# S7CAS-PLEIADES-CARTE-MERE_Pxx_FLASH_PHY_.net
KiCad netlist of a schematic drawn in Altium Designer
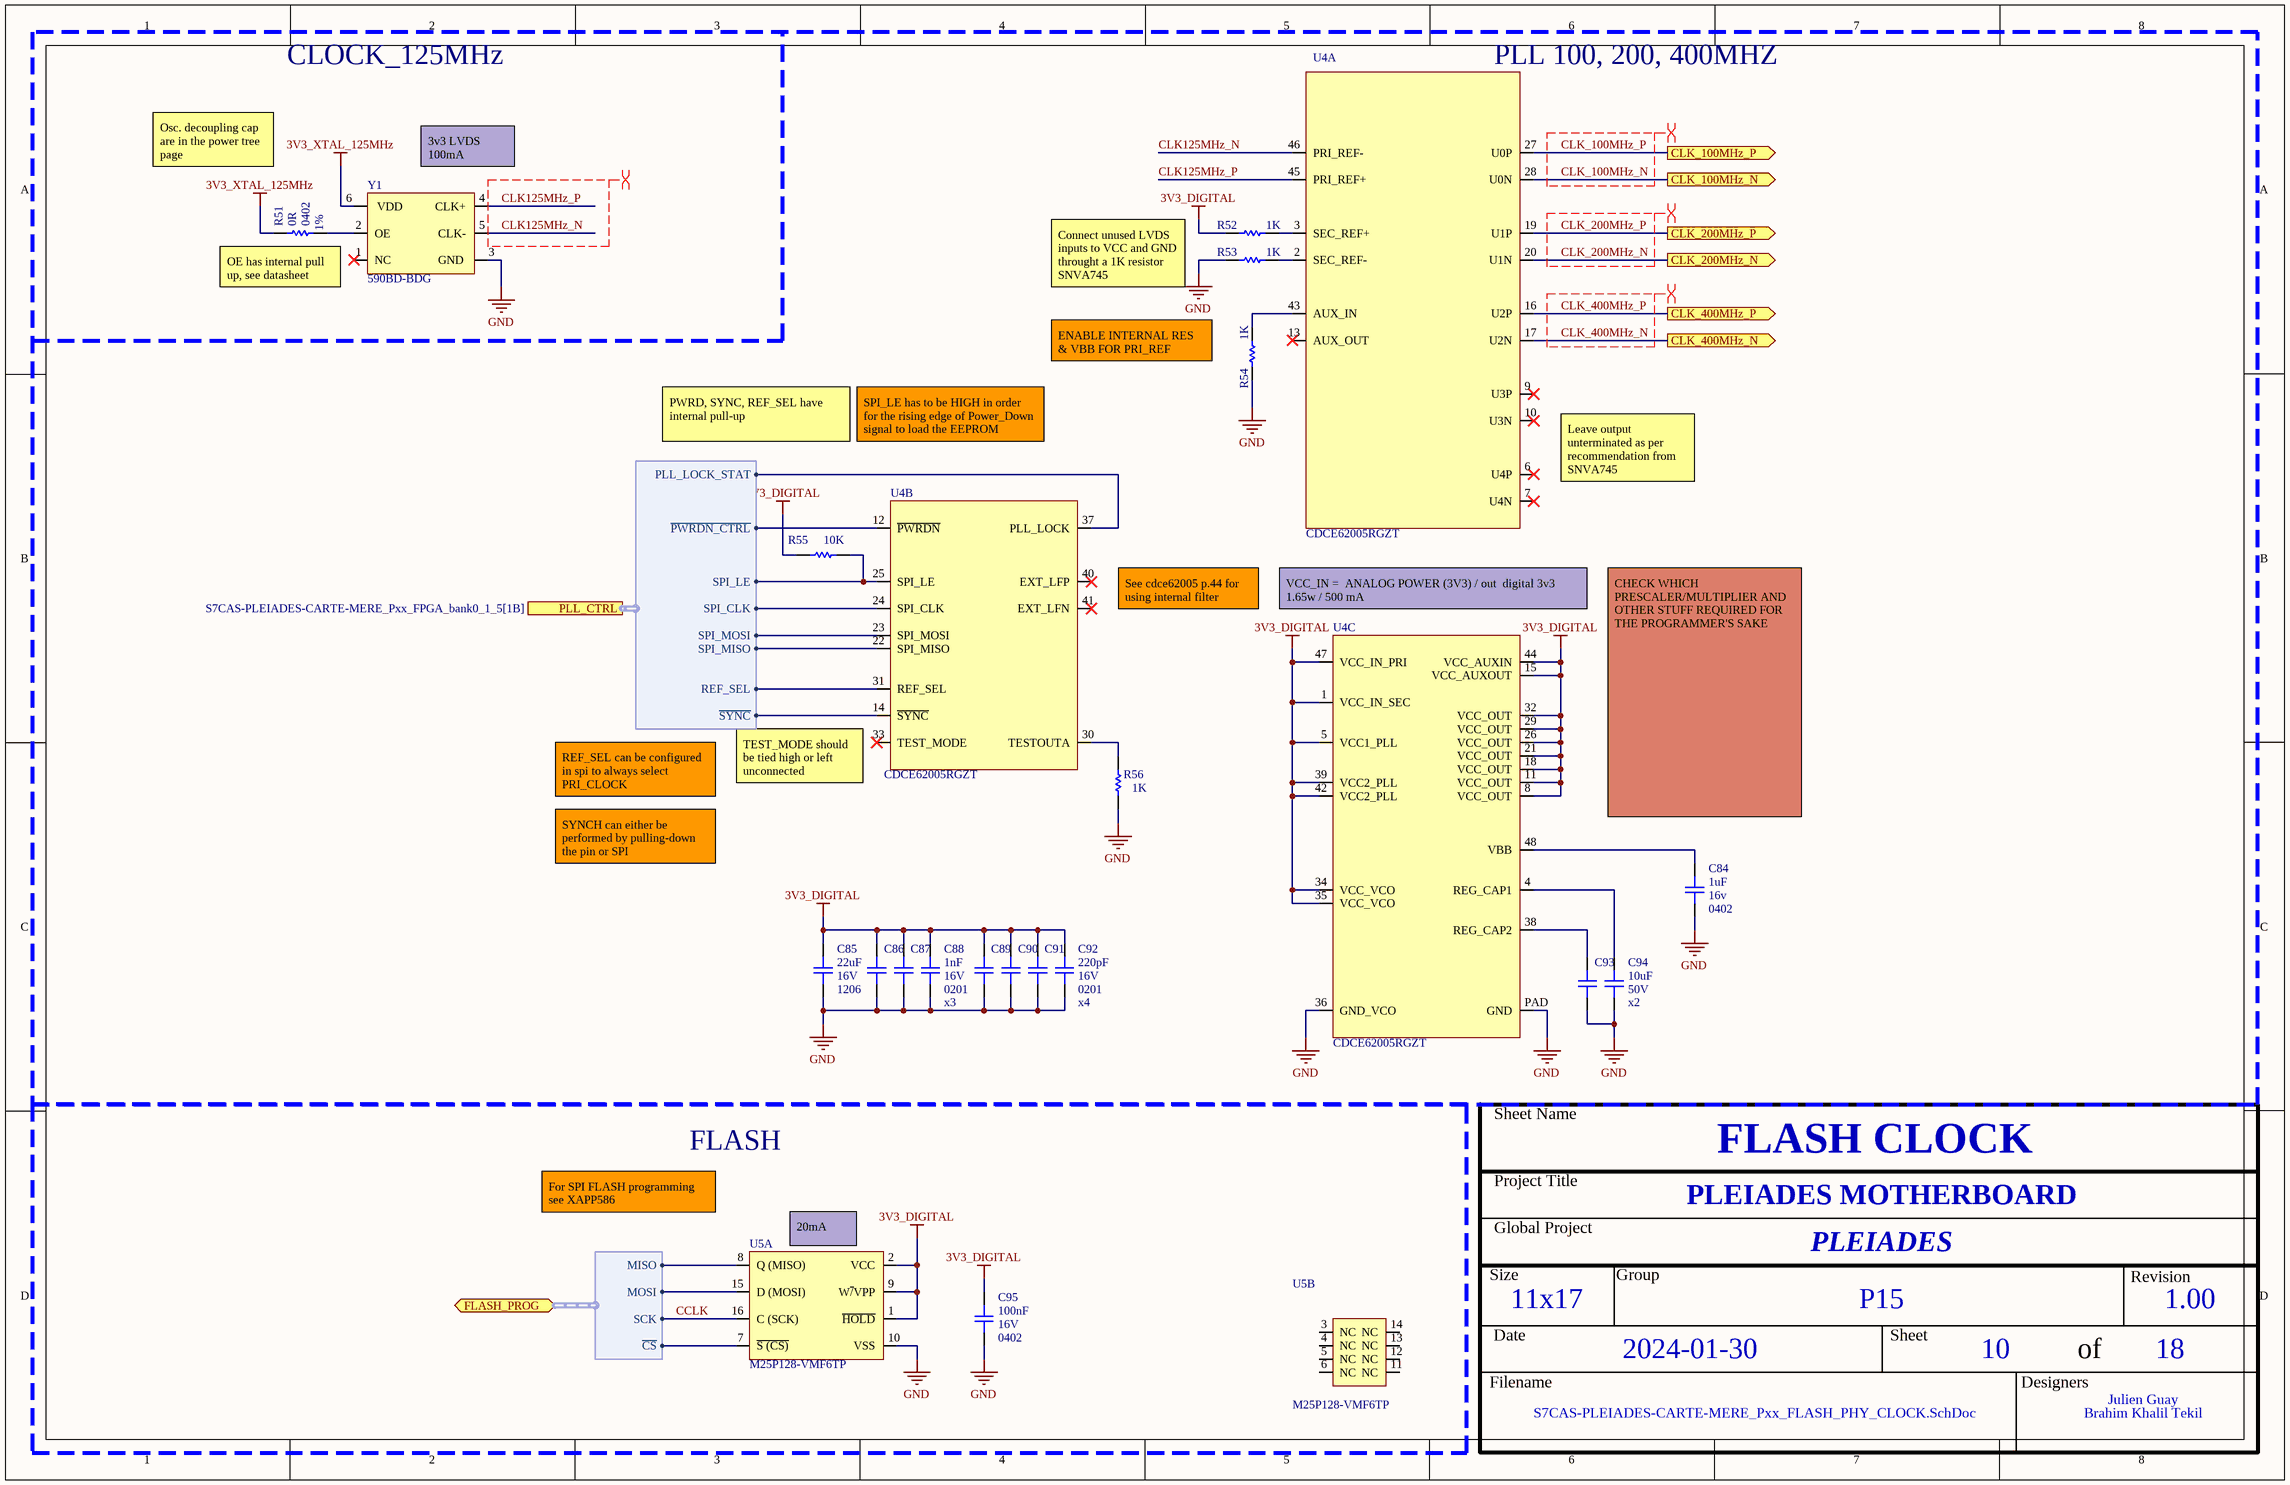
[diagram p0: S7CAS-PLEIADES-CARTE-MERE_Pxx_FLASH_PHY_CLOCK.SchDoc]

(export (version "E")
  (design (tool "Eeschema 10.0.6"))
  (components
    (comp (ref "C84")
      (value "1uF")
      (footprint "S7CAS_LIB2023:CAP_0402")
      (description "CAP - 0402")
      (fields
        (field (name "VOLTAGE") "16v")
        (field (name "PACKAGE") "0402")
        (field (name "Comment") "0402")
        (field (name "CREATEDBY") "Jonathan Bouchard")
      )
      (libsource (lib "S7CAS_LIB2023") (part "CAP - 0603"))
    )
    (comp (ref "C85")
      (value "22uF")
      (footprint "S7CAS_LIB2023:CAP_1206")
      (description "CAP - 1206")
      (fields
        (field (name "VOLTAGE") "16V")
        (field (name "PACKAGE") "1206")
        (field (name "CREATEDBY") "Jonathan Bouchard")
      )
      (libsource (lib "S7CAS_LIB2023") (part "CAP - 1206"))
    )
    (comp (ref "C86")
      (value "CAP - 0201")
      (footprint "CAP_0201")
      (fields (field (name "VOLTAGE") "16V") (field (name "CREATEDBY") "Jonathan Bouchard"))
      (libsource (lib "S7CAS_LIB2023") (part "CAP - 0201"))
    )
    (comp (ref "C87")
      (value "CAP - 0201")
      (footprint "CAP_0201")
      (fields (field (name "VOLTAGE") "16V") (field (name "CREATEDBY") "Jonathan Bouchard"))
      (libsource (lib "S7CAS_LIB2023") (part "CAP - 0201"))
    )
    (comp (ref "C88")
      (value "1nF")
      (footprint "CAP_0201")
      (description "CAP - 0201")
      (fields
        (field (name "VOLTAGE") "16V")
        (field (name "PACKAGE") "0201")
        (field (name "CREATEDBY") "Jonathan Bouchard")
      )
      (libsource (lib "S7CAS_LIB2023") (part "CAP - 0201"))
    )
    (comp (ref "C89")
      (value "CAP - 0201")
      (footprint "CAP_0201")
      (fields (field (name "VOLTAGE") "16V") (field (name "CREATEDBY") "Jonathan Bouchard"))
      (libsource (lib "S7CAS_LIB2023") (part "CAP - 0201"))
    )
    (comp (ref "C90")
      (value "CAP - 0201")
      (footprint "CAP_0201")
      (fields (field (name "VOLTAGE") "16V") (field (name "CREATEDBY") "Jonathan Bouchard"))
      (libsource (lib "S7CAS_LIB2023") (part "CAP - 0201"))
    )
    (comp (ref "C91")
      (value "CAP - 0201")
      (footprint "CAP_0201")
      (fields (field (name "VOLTAGE") "16V") (field (name "CREATEDBY") "Jonathan Bouchard"))
      (libsource (lib "S7CAS_LIB2023") (part "CAP - 0201"))
    )
    (comp (ref "C92")
      (value "220pF")
      (footprint "CAP_0201")
      (description "CAP - 0201")
      (fields
        (field (name "VOLTAGE") "16V")
        (field (name "PACKAGE") "0201")
        (field (name "CREATEDBY") "Jonathan Bouchard")
      )
      (libsource (lib "S7CAS_LIB2023") (part "CAP - 0201"))
    )
    (comp (ref "C93")
      (value "CAP - 1206")
      (footprint "S7CAS_LIB2023:CAP_1206")
      (fields (field (name "VOLTAGE") "50V") (field (name "CREATEDBY") "Jonathan Bouchard"))
      (libsource (lib "S7CAS_LIB2023") (part "CAP - 1206"))
    )
    (comp (ref "C94")
      (value "10uF")
      (footprint "S7CAS_LIB2023:CAP_1206")
      (description "CAP - 1206")
      (fields (field (name "VOLTAGE") "50V") (field (name "CREATEDBY") "Jonathan Bouchard"))
      (libsource (lib "S7CAS_LIB2023") (part "CAP - 1206"))
    )
    (comp (ref "C95")
      (value "100nF")
      (footprint "S7CAS_LIB2023:CAP_0402")
      (description "CAP - 0402")
      (fields
        (field (name "VOLTAGE") "16V")
        (field (name "PACKAGE") "0402")
        (field (name "Comment") "0402")
        (field (name "CREATEDBY") "Jonathan Bouchard")
      )
      (libsource (lib "S7CAS_LIB2023") (part "CAP - 0603"))
    )
    (comp (ref "R51")
      (value "0R")
      (footprint "S7CAS_LIB2023:RES_0402")
      (description "RES - 0402")
      (fields
        (field (name "PACKAGE") "0402")
        (field (name "PRECISION") "1%")
        (field (name "Comment") "RES - 0603")
        (field (name "CREATEDBY") "Jonathan Bouchard")
      )
      (libsource (lib "S7CAS_LIB2023") (part "RES - 0603"))
    )
    (comp (ref "R52")
      (value "1K")
      (footprint "S7CAS_LIB2023:RES_0402")
      (description "RES - 0402")
      (fields (field (name "Comment") "RES - 0603") (field (name "CREATEDBY") "Jonathan Bouchard"))
      (libsource (lib "S7CAS_LIB2023") (part "RES - 0603"))
    )
    (comp (ref "R53")
      (value "1K")
      (footprint "S7CAS_LIB2023:RES_0402")
      (description "RES - 0402")
      (fields (field (name "Comment") "RES - 0603") (field (name "CREATEDBY") "Jonathan Bouchard"))
      (libsource (lib "S7CAS_LIB2023") (part "RES - 0603"))
    )
    (comp (ref "R54")
      (value "1K")
      (footprint "S7CAS_LIB2023:RES_0402")
      (description "RES - 0402")
      (fields (field (name "Comment") "RES - 0603") (field (name "CREATEDBY") "Jonathan Bouchard"))
      (libsource (lib "S7CAS_LIB2023") (part "RES - 0603"))
    )
    (comp (ref "R55")
      (value "10K")
      (footprint "S7CAS_LIB2023:RES_0402")
      (description "RES - 0402")
      (fields (field (name "Comment") "RES - 0603") (field (name "CREATEDBY") "Jonathan Bouchard"))
      (libsource (lib "S7CAS_LIB2023") (part "RES - 0603"))
    )
    (comp (ref "R56")
      (value "1K")
      (footprint "S7CAS_LIB2023:RES_0402")
      (description "RES - 0402")
      (fields (field (name "Comment") "RES - 0603") (field (name "CREATEDBY") "Jonathan Bouchard"))
      (libsource (lib "S7CAS_LIB2023") (part "RES - 0603"))
    )
    (comp (ref "U4")
      (value "CDCE62005RGZT")
      (footprint "TIM_CDCE62005RGZT")
      (description "TIM - CLK SYNTH JITTER CLEANER 3:5 - QFN-48")
      (fields
        (field (name "VOLTAGE") "3 V ~ 3.6 V")
        (field (name "MFG") "Texas Instruments")
        (field (name "CREATEDBY") "Jonathan Bouchard")
      )
      (libsource (lib "S7CAS_LIB2023") (part "TIM_CDCE62005RGZT"))
    )
    (comp (ref "U5")
      (value "M25P128-VMF6TP")
      (footprint "FLASH - M25P128-VMF6TP")
      (description "128-Mbit, low-voltage, serial flash memory\r\nwith 54-MHz SPI bus interface")
      (libsource (lib "S7CAS_LIB2023") (part "FLASH  - M25P128-VMF6TP"))
    )
    (comp (ref "Y1")
      (value "590BD-BDG")
      (footprint "OSC_590BD-BDG")
      (description "TIM - OSC PROG 125MHz ~ 214.999MHz LVDS 3.3V 7PPM EN/DS - 6-SMD")
      (fields
        (field (name "CREATEDBY/DATE") "from 590BD-CDG")
        (field (name "VERIFIEDBY") "Caroline Paulin / 3/10/2019")
      )
      (libsource (lib "S7CAS_LIB2023") (part "OSC_590BD-BDG"))
    )
  )
  (nets
    (net (code "3") (name "/CCLK") (class "Default")
      (node (ref "U5") (pin "16") (pinfunction "C_(SCK)_16") (pintype "passive"))
    )
    (net (code "4") (name "/CLK125MHz_N") (class "Default")
      (node (ref "U4") (pin "46") (pinfunction "PRI_REF-_46") (pintype "passive"))
      (node (ref "Y1") (pin "5") (pinfunction "CLK-_5") (pintype "passive"))
    )
    (net (code "5") (name "/CLK125MHz_P") (class "Default")
      (node (ref "U4") (pin "45") (pinfunction "PRI_REF+_45") (pintype "passive"))
      (node (ref "Y1") (pin "4") (pinfunction "CLK+_4") (pintype "passive"))
    )
    (net (code "6") (name "/CLK_100MHz_N") (class "Default")
      (node (ref "U4") (pin "28") (pinfunction "U0N_28") (pintype "passive"))
    )
    (net (code "7") (name "/CLK_100MHz_P") (class "Default")
      (node (ref "U4") (pin "27") (pinfunction "U0P_27") (pintype "passive"))
    )
    (net (code "8") (name "/CLK_200MHz_N") (class "Default")
      (node (ref "U4") (pin "20") (pinfunction "U1N_20") (pintype "passive"))
    )
    (net (code "9") (name "/CLK_200MHz_P") (class "Default")
      (node (ref "U4") (pin "19") (pinfunction "U1P_19") (pintype "passive"))
    )
    (net (code "10") (name "/CLK_400MHz_N") (class "Default")
      (node (ref "U4") (pin "17") (pinfunction "U2N_17") (pintype "passive"))
    )
    (net (code "11") (name "/CLK_400MHz_P") (class "Default")
      (node (ref "U4") (pin "16") (pinfunction "U2P_16") (pintype "passive"))
    )
    (net (code "12") (name "/MISO") (class "Default")
      (node (ref "U5") (pin "8") (pinfunction "Q_(MISO)_8") (pintype "passive"))
    )
    (net (code "13") (name "/MOSI") (class "Default")
      (node (ref "U5") (pin "15") (pinfunction "D_(MOSI)_15") (pintype "passive"))
    )
    (net (code "14") (name "/PLL_LOCK_STAT") (class "Default")
      (node (ref "U4") (pin "37") (pinfunction "PLL_LOCK_37") (pintype "passive"))
    )
    (net (code "15") (name "/REF_SEL") (class "Default")
      (node (ref "U4") (pin "31") (pinfunction "REF_SEL_31") (pintype "passive"))
    )
    (net (code "16") (name "/SPI_CLK") (class "Default")
      (node (ref "U4") (pin "24") (pinfunction "SPI_CLK_24") (pintype "passive"))
    )
    (net (code "17") (name "/SPI_LE") (class "Default")
      (node (ref "R55") (pin "1") (pinfunction "1_1") (pintype "passive"))
      (node (ref "U4") (pin "25") (pinfunction "SPI_LE_25") (pintype "passive"))
    )
    (net (code "18") (name "/SPI_MISO") (class "Default")
      (node (ref "U4") (pin "22") (pinfunction "SPI_MISO_22") (pintype "passive"))
    )
    (net (code "19") (name "/SPI_MOSI") (class "Default")
      (node (ref "U4") (pin "23") (pinfunction "SPI_MOSI_23") (pintype "passive"))
    )
    (net (code "22") (name "/~{CS}") (class "Default")
      (node (ref "U5") (pin "7") (pinfunction "S_(CS)_7") (pintype "passive"))
    )
    (net (code "23") (name "/~{PWRDN_CTRL}") (class "Default")
      (node (ref "U4") (pin "12") (pinfunction "~{PWRDN}_12") (pintype "passive"))
    )
    (net (code "24") (name "/~{SYNC}") (class "Default")
      (node (ref "U4") (pin "14") (pinfunction "~{SYNC}_14") (pintype "passive"))
    )
    (net (code "25") (name "3V3_DIGITAL") (class "Default")
      (node (ref "C85") (pin "2") (pinfunction "2_2") (pintype "passive"))
      (node (ref "C86") (pin "2") (pinfunction "2_2") (pintype "passive"))
      (node (ref "C87") (pin "2") (pinfunction "2_2") (pintype "passive"))
      (node (ref "C88") (pin "2") (pinfunction "2_2") (pintype "passive"))
      (node (ref "C89") (pin "2") (pinfunction "2_2") (pintype "passive"))
      (node (ref "C90") (pin "2") (pinfunction "2_2") (pintype "passive"))
      (node (ref "C91") (pin "2") (pinfunction "2_2") (pintype "passive"))
      (node (ref "C92") (pin "2") (pinfunction "2_2") (pintype "passive"))
      (node (ref "C95") (pin "2") (pinfunction "2_2") (pintype "passive"))
      (node (ref "R52") (pin "2") (pinfunction "2_2") (pintype "passive"))
      (node (ref "R55") (pin "2") (pinfunction "2_2") (pintype "passive"))
      (node (ref "U4") (pin "1") (pinfunction "VCC_IN_SEC_1") (pintype "passive"))
      (node (ref "U4") (pin "11") (pinfunction "VCC_OUT_11") (pintype "passive"))
      (node (ref "U4") (pin "15") (pinfunction "VCC_AUXOUT_15") (pintype "passive"))
      (node (ref "U4") (pin "18") (pinfunction "VCC_OUT_18") (pintype "passive"))
      (node (ref "U4") (pin "21") (pinfunction "VCC_OUT_21") (pintype "passive"))
      (node (ref "U4") (pin "26") (pinfunction "VCC_OUT_26") (pintype "passive"))
      (node (ref "U4") (pin "29") (pinfunction "VCC_OUT_29") (pintype "passive"))
      (node (ref "U4") (pin "32") (pinfunction "VCC_OUT_32") (pintype "passive"))
      (node (ref "U4") (pin "34") (pinfunction "VCC_VCO_34") (pintype "passive"))
      (node (ref "U4") (pin "35") (pinfunction "VCC_VCO_35") (pintype "passive"))
      (node (ref "U4") (pin "39") (pinfunction "VCC2_PLL_39") (pintype "passive"))
      (node (ref "U4") (pin "42") (pinfunction "VCC2_PLL_42") (pintype "passive"))
      (node (ref "U4") (pin "44") (pinfunction "VCC_AUXIN_44") (pintype "passive"))
      (node (ref "U4") (pin "47") (pinfunction "VCC_IN_PRI_47") (pintype "passive"))
      (node (ref "U4") (pin "5") (pinfunction "VCC1_PLL_5") (pintype "passive"))
      (node (ref "U4") (pin "8") (pinfunction "VCC_OUT_8") (pintype "passive"))
      (node (ref "U5") (pin "1") (pinfunction "HOLD_1") (pintype "passive"))
      (node (ref "U5") (pin "2") (pinfunction "VCC_2") (pintype "power_in"))
      (node (ref "U5") (pin "9") (pinfunction "W~{/}VPP_9") (pintype "passive"))
    )
    (net (code "26") (name "3V3_XTAL_125MHz") (class "Default")
      (node (ref "R51") (pin "2") (pinfunction "2_2") (pintype "passive"))
      (node (ref "Y1") (pin "6") (pinfunction "VDD_6") (pintype "passive"))
    )
    (net (code "27") (name "GND") (class "Default")
      (node (ref "C84") (pin "1") (pinfunction "1_1") (pintype "passive"))
      (node (ref "C85") (pin "1") (pinfunction "1_1") (pintype "passive"))
      (node (ref "C86") (pin "1") (pinfunction "1_1") (pintype "passive"))
      (node (ref "C87") (pin "1") (pinfunction "1_1") (pintype "passive"))
      (node (ref "C88") (pin "1") (pinfunction "1_1") (pintype "passive"))
      (node (ref "C89") (pin "1") (pinfunction "1_1") (pintype "passive"))
      (node (ref "C90") (pin "1") (pinfunction "1_1") (pintype "passive"))
      (node (ref "C91") (pin "1") (pinfunction "1_1") (pintype "passive"))
      (node (ref "C92") (pin "1") (pinfunction "1_1") (pintype "passive"))
      (node (ref "C93") (pin "1") (pinfunction "1_1") (pintype "passive"))
      (node (ref "C94") (pin "1") (pinfunction "1_1") (pintype "passive"))
      (node (ref "C95") (pin "1") (pinfunction "1_1") (pintype "passive"))
      (node (ref "R53") (pin "2") (pinfunction "2_2") (pintype "passive"))
      (node (ref "R54") (pin "2") (pinfunction "2_2") (pintype "passive"))
      (node (ref "R56") (pin "1") (pinfunction "1_1") (pintype "passive"))
      (node (ref "U4") (pin "36") (pinfunction "GND_VCO_36") (pintype "passive"))
      (node (ref "U4") (pin "PAD") (pinfunction "GND_PAD") (pintype "passive"))
      (node (ref "U5") (pin "10") (pinfunction "VSS_10") (pintype "power_in"))
      (node (ref "Y1") (pin "3") (pinfunction "GND_3") (pintype "passive"))
    )
    (net (code "28") (name "Net-(U4A-AUX_IN)") (class "Default")
      (node (ref "R54") (pin "1") (pinfunction "1_1") (pintype "passive"))
      (node (ref "U4") (pin "43") (pinfunction "AUX_IN_43") (pintype "passive"))
    )
    (net (code "29") (name "Net-(U4A-SEC_REF+)") (class "Default")
      (node (ref "R52") (pin "1") (pinfunction "1_1") (pintype "passive"))
      (node (ref "U4") (pin "3") (pinfunction "SEC_REF+_3") (pintype "passive"))
    )
    (net (code "30") (name "Net-(U4A-SEC_REF-)") (class "Default")
      (node (ref "R53") (pin "1") (pinfunction "1_1") (pintype "passive"))
      (node (ref "U4") (pin "2") (pinfunction "SEC_REF-_2") (pintype "passive"))
    )
    (net (code "31") (name "Net-(U4B-TESTOUTA)") (class "Default")
      (node (ref "R56") (pin "2") (pinfunction "2_2") (pintype "passive"))
      (node (ref "U4") (pin "30") (pinfunction "TESTOUTA_30") (pintype "passive"))
    )
    (net (code "32") (name "Net-(U4C-REG_CAP1)") (class "Default")
      (node (ref "C94") (pin "2") (pinfunction "2_2") (pintype "passive"))
      (node (ref "U4") (pin "4") (pinfunction "REG_CAP1_4") (pintype "passive"))
    )
    (net (code "33") (name "Net-(U4C-REG_CAP2)") (class "Default")
      (node (ref "C93") (pin "2") (pinfunction "2_2") (pintype "passive"))
      (node (ref "U4") (pin "38") (pinfunction "REG_CAP2_38") (pintype "passive"))
    )
    (net (code "34") (name "Net-(U4C-VBB)") (class "Default")
      (node (ref "C84") (pin "2") (pinfunction "2_2") (pintype "passive"))
      (node (ref "U4") (pin "48") (pinfunction "VBB_48") (pintype "passive"))
    )
    (net (code "35") (name "Net-(Y1-OE)") (class "Default")
      (node (ref "R51") (pin "1") (pinfunction "1_1") (pintype "passive"))
      (node (ref "Y1") (pin "2") (pinfunction "OE_2") (pintype "passive"))
    )
    (net (code "36") (name "unconnected-(U4A-AUX_OUT-Pad13)") (class "Default")
      (node (ref "U4") (pin "13") (pinfunction "AUX_OUT_13") (pintype "passive+no_connect"))
    )
    (net (code "37") (name "unconnected-(U4A-U3N-Pad10)") (class "Default")
      (node (ref "U4") (pin "10") (pinfunction "U3N_10") (pintype "passive+no_connect"))
    )
    (net (code "38") (name "unconnected-(U4A-U3P-Pad9)") (class "Default")
      (node (ref "U4") (pin "9") (pinfunction "U3P_9") (pintype "passive+no_connect"))
    )
    (net (code "39") (name "unconnected-(U4A-U4N-Pad7)") (class "Default")
      (node (ref "U4") (pin "7") (pinfunction "U4N_7") (pintype "passive+no_connect"))
    )
    (net (code "40") (name "unconnected-(U4A-U4P-Pad6)") (class "Default")
      (node (ref "U4") (pin "6") (pinfunction "U4P_6") (pintype "passive+no_connect"))
    )
    (net (code "41") (name "unconnected-(U4B-EXT_LFN-Pad41)") (class "Default")
      (node (ref "U4") (pin "41") (pinfunction "EXT_LFN_41") (pintype "passive+no_connect"))
    )
    (net (code "42") (name "unconnected-(U4B-EXT_LFP-Pad40)") (class "Default")
      (node (ref "U4") (pin "40") (pinfunction "EXT_LFP_40") (pintype "passive+no_connect"))
    )
    (net (code "43") (name "unconnected-(U4B-TEST_MODE-Pad33)") (class "Default")
      (node (ref "U4") (pin "33") (pinfunction "TEST_MODE_33") (pintype "passive+no_connect"))
    )
    (net (code "44") (name "unconnected-(U5B-NC-Pad3)") (class "Default")
      (node (ref "U5") (pin "3") (pinfunction "NC_3") (pintype "passive"))
    )
    (net (code "45") (name "unconnected-(U5B-NC-Pad4)") (class "Default")
      (node (ref "U5") (pin "4") (pinfunction "NC_4") (pintype "passive"))
    )
    (net (code "46") (name "unconnected-(U5B-NC-Pad5)") (class "Default")
      (node (ref "U5") (pin "5") (pinfunction "NC_5") (pintype "passive"))
    )
    (net (code "47") (name "unconnected-(U5B-NC-Pad6)") (class "Default")
      (node (ref "U5") (pin "6") (pinfunction "NC_6") (pintype "passive"))
    )
    (net (code "48") (name "unconnected-(U5B-NC-Pad11)") (class "Default")
      (node (ref "U5") (pin "11") (pinfunction "NC_11") (pintype "passive"))
    )
    (net (code "49") (name "unconnected-(U5B-NC-Pad12)") (class "Default")
      (node (ref "U5") (pin "12") (pinfunction "NC_12") (pintype "passive"))
    )
    (net (code "50") (name "unconnected-(U5B-NC-Pad13)") (class "Default")
      (node (ref "U5") (pin "13") (pinfunction "NC_13") (pintype "passive"))
    )
    (net (code "51") (name "unconnected-(U5B-NC-Pad14)") (class "Default")
      (node (ref "U5") (pin "14") (pinfunction "NC_14") (pintype "passive"))
    )
    (net (code "52") (name "unconnected-(Y1-NC-Pad1)") (class "Default")
      (node (ref "Y1") (pin "1") (pinfunction "NC_1") (pintype "passive+no_connect"))
    )
  )
)
